# RS232.net
KiCad netlist of a schematic drawn in Altium Designer
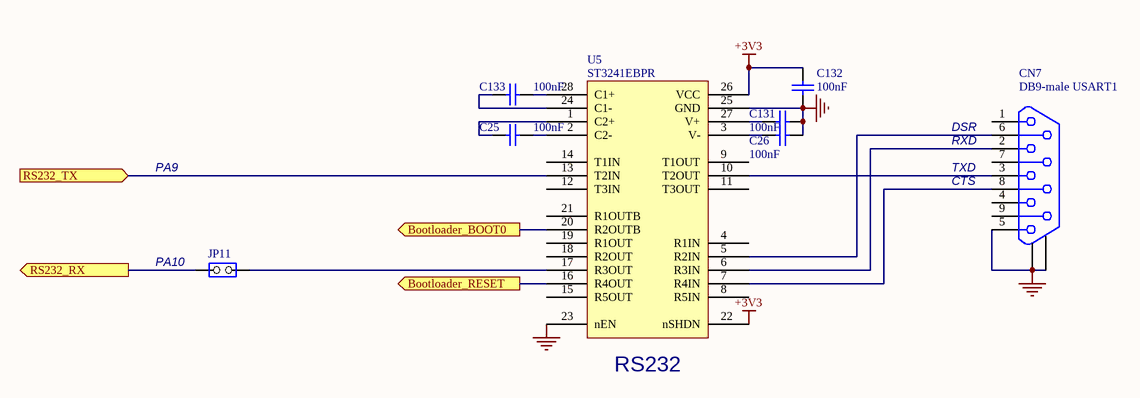
[diagram p0: RS232.SchDoc]

(export (version "E")
  (design (tool "Eeschema 10.0.6"))
  (components
    (comp (ref "C25")
      (value "100nF")
      (footprint "0603C")
      (description "Capacitor")
      (fields (field (name "PUBLISHER") "Altium Limited"))
      (libsource (lib "Miscellaneous Devices") (part "Cap"))
    )
    (comp (ref "C26")
      (value "100nF")
      (footprint "0603C")
      (description "Capacitor")
      (fields (field (name "PUBLISHER") "Altium Limited"))
      (libsource (lib "Miscellaneous Devices") (part "Cap"))
    )
    (comp (ref "C131")
      (value "100nF")
      (footprint "0603C")
      (description "Capacitor")
      (fields (field (name "PUBLISHER") "Altium Limited"))
      (libsource (lib "Miscellaneous Devices") (part "Cap"))
    )
    (comp (ref "C132")
      (value "100nF")
      (footprint "0603C")
      (description "Capacitor")
      (fields (field (name "PUBLISHER") "Altium Limited"))
      (libsource (lib "Miscellaneous Devices") (part "Cap"))
    )
    (comp (ref "C133")
      (value "100nF")
      (footprint "0603C")
      (description "Capacitor")
      (fields (field (name "PUBLISHER") "Altium Limited"))
      (libsource (lib "Miscellaneous Devices") (part "Cap"))
    )
    (comp (ref "CN7")
      (value "DB9-male USART1")
      (footprint "DB9/M")
      (libsource (lib "MB1219") (part "DB9-USART"))
    )
    (comp (ref "JP11") (value "~") (footprint "SIP2") (libsource (lib "*") (part "JP2")))
    (comp (ref "U5")
      (value "ST3241EBPR")
      (footprint "SSOP28_0R65_10R2X7R8")
      (libsource (lib "MB1219") (part "ST3241EBPR"))
    )
  )
  (nets
    (net (code "1") (name "+3V3") (class "Default")
      (node (ref "C132") (pin "1") (pinfunction "1_1") (pintype "passive"))
      (node (ref "U5") (pin "22") (pinfunction "nSHDN_22") (pintype "passive"))
      (node (ref "U5") (pin "26") (pinfunction "VCC_26") (pintype "passive"))
    )
    (net (code "2") (name "/Bootloader_BOOT0") (class "Default")
      (node (ref "U5") (pin "20") (pinfunction "R2OUTB_20") (pintype "passive"))
    )
    (net (code "3") (name "/Bootloader_RESET") (class "Default")
      (node (ref "U5") (pin "16") (pinfunction "R4OUT_16") (pintype "passive"))
    )
    (net (code "4") (name "/RS232_RX") (class "Default")
      (node (ref "JP11") (pin "1") (pinfunction "COMMON_1") (pintype "passive"))
    )
    (net (code "5") (name "/RS232_TX") (class "Default")
      (node (ref "U5") (pin "13") (pinfunction "T2IN_13") (pintype "passive"))
    )
    (net (code "6") (name "GND") (class "Default")
      (node (ref "C131") (pin "1") (pinfunction "1_1") (pintype "passive"))
      (node (ref "C132") (pin "2") (pinfunction "2_2") (pintype "passive"))
      (node (ref "C26") (pin "1") (pinfunction "1_1") (pintype "passive"))
      (node (ref "CN7") (pin "10") (pinfunction "10_10") (pintype "passive"))
      (node (ref "CN7") (pin "11") (pinfunction "11_11") (pintype "passive"))
      (node (ref "CN7") (pin "5") (pinfunction "5_5") (pintype "passive"))
      (node (ref "U5") (pin "23") (pinfunction "nEN_23") (pintype "passive"))
      (node (ref "U5") (pin "25") (pinfunction "GND_25") (pintype "passive"))
    )
    (net (code "7") (name "Net-(JP11-NO)") (class "Default")
      (node (ref "JP11") (pin "2") (pinfunction "NO_2") (pintype "passive"))
      (node (ref "U5") (pin "17") (pinfunction "R3OUT_17") (pintype "passive"))
    )
    (net (code "8") (name "Net-(U5-C1+)") (class "Default")
      (node (ref "C133") (pin "2") (pinfunction "2_2") (pintype "passive"))
      (node (ref "U5") (pin "28") (pinfunction "C1+_28") (pintype "passive"))
    )
    (net (code "9") (name "Net-(U5-C1-)") (class "Default")
      (node (ref "C133") (pin "1") (pinfunction "1_1") (pintype "passive"))
      (node (ref "U5") (pin "24") (pinfunction "C1-_24") (pintype "passive"))
    )
    (net (code "10") (name "Net-(U5-C2+)") (class "Default")
      (node (ref "C25") (pin "1") (pinfunction "1_1") (pintype "passive"))
      (node (ref "U5") (pin "1") (pinfunction "C2+_1") (pintype "passive"))
    )
    (net (code "11") (name "Net-(U5-C2-)") (class "Default")
      (node (ref "C25") (pin "2") (pinfunction "2_2") (pintype "passive"))
      (node (ref "U5") (pin "2") (pinfunction "C2-_2") (pintype "passive"))
    )
    (net (code "12") (name "Net-(U5-R2IN)") (class "Default")
      (node (ref "CN7") (pin "6") (pinfunction "6_6") (pintype "passive"))
      (node (ref "U5") (pin "5") (pinfunction "R2IN_5") (pintype "passive"))
    )
    (net (code "13") (name "Net-(U5-R3IN)") (class "Default")
      (node (ref "CN7") (pin "2") (pinfunction "2_2") (pintype "passive"))
      (node (ref "U5") (pin "6") (pinfunction "R3IN_6") (pintype "passive"))
    )
    (net (code "14") (name "Net-(U5-R4IN)") (class "Default")
      (node (ref "CN7") (pin "8") (pinfunction "8_8") (pintype "passive"))
      (node (ref "U5") (pin "7") (pinfunction "R4IN_7") (pintype "passive"))
    )
    (net (code "15") (name "Net-(U5-T2OUT)") (class "Default")
      (node (ref "CN7") (pin "3") (pinfunction "3_3") (pintype "passive"))
      (node (ref "U5") (pin "10") (pinfunction "T2OUT_10") (pintype "passive"))
    )
    (net (code "16") (name "Net-(U5-V+)") (class "Default")
      (node (ref "C131") (pin "2") (pinfunction "2_2") (pintype "passive"))
      (node (ref "U5") (pin "27") (pinfunction "V+_27") (pintype "passive"))
    )
    (net (code "17") (name "Net-(U5-V-)") (class "Default")
      (node (ref "C26") (pin "2") (pinfunction "2_2") (pintype "passive"))
      (node (ref "U5") (pin "3") (pinfunction "V-_3") (pintype "passive"))
    )
    (net (code "18") (name "unconnected-(CN7-Pad1)") (class "Default")
      (node (ref "CN7") (pin "1") (pinfunction "1_1") (pintype "passive"))
    )
    (net (code "19") (name "unconnected-(CN7-Pad4)") (class "Default")
      (node (ref "CN7") (pin "4") (pinfunction "4_4") (pintype "passive"))
    )
    (net (code "20") (name "unconnected-(CN7-Pad7)") (class "Default")
      (node (ref "CN7") (pin "7") (pinfunction "7_7") (pintype "passive"))
    )
    (net (code "21") (name "unconnected-(CN7-Pad9)") (class "Default")
      (node (ref "CN7") (pin "9") (pinfunction "9_9") (pintype "passive"))
    )
    (net (code "22") (name "unconnected-(U5-R1IN-Pad4)") (class "Default")
      (node (ref "U5") (pin "4") (pinfunction "R1IN_4") (pintype "passive"))
    )
    (net (code "23") (name "unconnected-(U5-R1OUT-Pad19)") (class "Default")
      (node (ref "U5") (pin "19") (pinfunction "R1OUT_19") (pintype "passive"))
    )
    (net (code "24") (name "unconnected-(U5-R1OUTB-Pad21)") (class "Default")
      (node (ref "U5") (pin "21") (pinfunction "R1OUTB_21") (pintype "passive"))
    )
    (net (code "25") (name "unconnected-(U5-R2OUT-Pad18)") (class "Default")
      (node (ref "U5") (pin "18") (pinfunction "R2OUT_18") (pintype "passive"))
    )
    (net (code "26") (name "unconnected-(U5-R5IN-Pad8)") (class "Default")
      (node (ref "U5") (pin "8") (pinfunction "R5IN_8") (pintype "passive"))
    )
    (net (code "27") (name "unconnected-(U5-R5OUT-Pad15)") (class "Default")
      (node (ref "U5") (pin "15") (pinfunction "R5OUT_15") (pintype "passive"))
    )
    (net (code "28") (name "unconnected-(U5-T1IN-Pad14)") (class "Default")
      (node (ref "U5") (pin "14") (pinfunction "T1IN_14") (pintype "passive"))
    )
    (net (code "29") (name "unconnected-(U5-T1OUT-Pad9)") (class "Default")
      (node (ref "U5") (pin "9") (pinfunction "T1OUT_9") (pintype "passive"))
    )
    (net (code "30") (name "unconnected-(U5-T3IN-Pad12)") (class "Default")
      (node (ref "U5") (pin "12") (pinfunction "T3IN_12") (pintype "passive"))
    )
    (net (code "31") (name "unconnected-(U5-T3OUT-Pad11)") (class "Default")
      (node (ref "U5") (pin "11") (pinfunction "T3OUT_11") (pintype "passive"))
    )
  )
)
